# CurruntGetter.net
KiCad netlist of a schematic drawn in Altium Designer
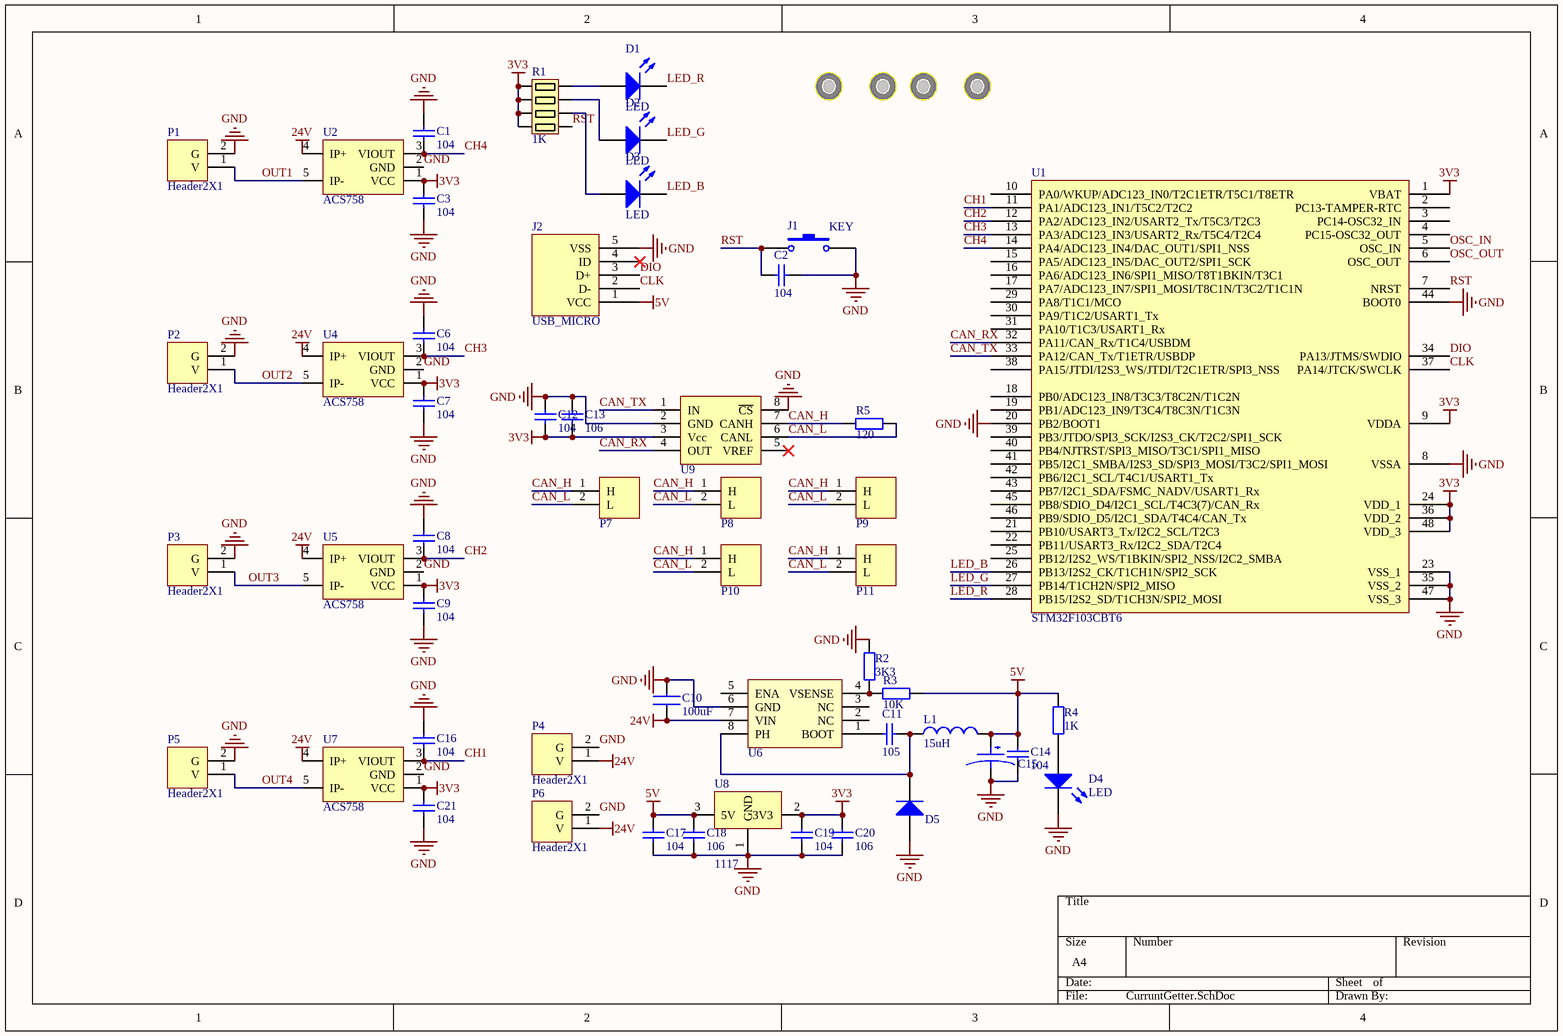
[diagram p0: CurruntGetter.SchDoc]

(export (version "E")
  (design (tool "Eeschema 10.0.6"))
  (components
    (comp (ref "1") (value "Via_M3") (footprint "Via_M3") (libsource (lib "SHAWN") (part "Via_M3")))
    (comp (ref "2") (value "Via_M3") (footprint "Via_M3") (libsource (lib "SHAWN") (part "Via_M3")))
    (comp (ref "3") (value "Via_M3") (footprint "Via_M3") (libsource (lib "SHAWN") (part "Via_M3")))
    (comp (ref "4") (value "Via_M3") (footprint "Via_M3") (libsource (lib "SHAWN") (part "Via_M3")))
    (comp (ref "C1")
      (value "104")
      (footprint "0603C")
      (description "0603/0805")
      (libsource (lib "SHAWN") (part "C_104"))
    )
    (comp (ref "C2")
      (value "104")
      (footprint "0603C")
      (description "0603/0805")
      (libsource (lib "SHAWN") (part "C_104"))
    )
    (comp (ref "C3")
      (value "104")
      (footprint "0603C")
      (description "0603/0805")
      (libsource (lib "SHAWN") (part "C_104"))
    )
    (comp (ref "C6")
      (value "104")
      (footprint "0603C")
      (description "0603/0805")
      (libsource (lib "SHAWN") (part "C_104"))
    )
    (comp (ref "C7")
      (value "104")
      (footprint "0603C")
      (description "0603/0805")
      (libsource (lib "SHAWN") (part "C_104"))
    )
    (comp (ref "C8")
      (value "104")
      (footprint "0603C")
      (description "0603/0805")
      (libsource (lib "SHAWN") (part "C_104"))
    )
    (comp (ref "C9")
      (value "104")
      (footprint "0603C")
      (description "0603/0805")
      (libsource (lib "SHAWN") (part "C_104"))
    )
    (comp (ref "C10") (value "100uF") (footprint "1201C") (libsource (lib "SHAWN") (part "CAP100uF")))
    (comp (ref "C11")
      (value "105")
      (footprint "0603C")
      (description "0603/0805")
      (libsource (lib "SHAWN") (part "C_104"))
    )
    (comp (ref "C12")
      (value "104")
      (footprint "0603C")
      (description "0603/0805")
      (libsource (lib "SHAWN") (part "C_104"))
    )
    (comp (ref "C13")
      (value "106")
      (footprint "0603C")
      (description "0603/0805")
      (libsource (lib "SHAWN") (part "C_106"))
    )
    (comp (ref "C14")
      (value "104")
      (footprint "0603C")
      (description "0603/0805")
      (libsource (lib "SHAWN") (part "C_104"))
    )
    (comp (ref "C15")
      (value "CAP_钽220")
      (footprint "cap_钽E封装")
      (description "CAP")
      (libsource (lib "SHAWN") (part "CAP_钽220"))
    )
    (comp (ref "C16")
      (value "104")
      (footprint "0603C")
      (description "0603/0805")
      (libsource (lib "SHAWN") (part "C_104"))
    )
    (comp (ref "C17")
      (value "104")
      (footprint "0603C")
      (description "0603/0805")
      (libsource (lib "SHAWN") (part "C_104"))
    )
    (comp (ref "C18")
      (value "106")
      (footprint "0603C")
      (description "0603/0805")
      (libsource (lib "SHAWN") (part "C_106"))
    )
    (comp (ref "C19")
      (value "104")
      (footprint "0603C")
      (description "0603/0805")
      (libsource (lib "SHAWN") (part "C_104"))
    )
    (comp (ref "C20")
      (value "106")
      (footprint "0603C")
      (description "0603/0805")
      (libsource (lib "SHAWN") (part "C_106"))
    )
    (comp (ref "C21")
      (value "104")
      (footprint "0603C")
      (description "0603/0805")
      (libsource (lib "SHAWN") (part "C_104"))
    )
    (comp (ref "D1") (value "LED") (footprint "LED_0603") (libsource (lib "SHAWN") (part "LED")))
    (comp (ref "D2") (value "LED") (footprint "LED_0603") (libsource (lib "SHAWN") (part "LED")))
    (comp (ref "D3") (value "LED") (footprint "LED_0603") (libsource (lib "SHAWN") (part "LED")))
    (comp (ref "D4") (value "LED") (footprint "LED_0603") (libsource (lib "SHAWN") (part "LED")))
    (comp (ref "D5")
      (value "Diode_SS34")
      (footprint "Diode_SS34")
      (description "肖特基二极管")
      (libsource (lib "SHAWN") (part "Diode_SS34"))
    )
    (comp (ref "J1") (value "KEY") (footprint "KEY") (libsource (lib "SHAWN") (part "KEY")))
    (comp (ref "J2") (value "USB_MICRO") (footprint "USB_MICRO") (libsource (lib "SHAWN") (part "USB_MICRO")))
    (comp (ref "L1")
      (value "15uH")
      (footprint "Inductor7.2X7.2")
      (description "屏蔽电感")
      (libsource (lib "SHAWN") (part "Inductor"))
    )
    (comp (ref "P1")
      (value "Header2X1")
      (footprint "Header_POWER")
      (description "power")
      (libsource (lib "SHAWN") (part "Header2X1"))
    )
    (comp (ref "P2")
      (value "Header2X1")
      (footprint "Header_POWER")
      (description "power")
      (libsource (lib "SHAWN") (part "Header2X1"))
    )
    (comp (ref "P3")
      (value "Header2X1")
      (footprint "Header_POWER")
      (description "power")
      (libsource (lib "SHAWN") (part "Header2X1"))
    )
    (comp (ref "P4")
      (value "Header2X1")
      (footprint "Header_POWER")
      (description "power")
      (libsource (lib "SHAWN") (part "Header2X1"))
    )
    (comp (ref "P5")
      (value "Header2X1")
      (footprint "Header_POWER")
      (description "power")
      (libsource (lib "SHAWN") (part "Header2X1"))
    )
    (comp (ref "P6")
      (value "Header2X1")
      (footprint "Header_POWER")
      (description "power")
      (libsource (lib "SHAWN") (part "Header2X1"))
    )
    (comp (ref "P7")
      (value "Header_CAN")
      (footprint "Header2_3002")
      (libsource (lib "SHAWN") (part "Header_CAN"))
    )
    (comp (ref "P8")
      (value "Header_CAN")
      (footprint "Header2_3002")
      (libsource (lib "SHAWN") (part "Header_CAN"))
    )
    (comp (ref "P9")
      (value "Header_CAN")
      (footprint "Header2_3002")
      (libsource (lib "SHAWN") (part "Header_CAN"))
    )
    (comp (ref "P10")
      (value "Header_CAN")
      (footprint "Header2_3002")
      (libsource (lib "SHAWN") (part "Header_CAN"))
    )
    (comp (ref "P11")
      (value "Header_CAN")
      (footprint "Header2_3002")
      (libsource (lib "SHAWN") (part "Header_CAN"))
    )
    (comp (ref "R1") (value "1K") (footprint "8P4R_0603") (libsource (lib "SHAWN") (part "R_8P4R")))
    (comp (ref "R2")
      (value "3K3")
      (footprint "0603R")
      (description "0603/0805")
      (libsource (lib "") (part "R_1"))
    )
    (comp (ref "R3")
      (value "10K")
      (footprint "0603R")
      (description "0603/0805")
      (libsource (lib "SHAWN") (part "R"))
    )
    (comp (ref "R4")
      (value "1K")
      (footprint "0603R")
      (description "0603/0805")
      (libsource (lib "") (part "R_1"))
    )
    (comp (ref "R5")
      (value "120")
      (footprint "0603R")
      (description "0603/0805")
      (libsource (lib "SHAWN") (part "R"))
    )
    (comp (ref "U1")
      (value "STM32F103CBT6")
      (footprint "LQFP_48")
      (description "48")
      (libsource (lib "SHAWN") (part "STM32F103CBT6"))
    )
    (comp (ref "U2") (value "ACS758") (footprint "PFF") (libsource (lib "SHAWN") (part "ACS758")))
    (comp (ref "U4") (value "ACS758") (footprint "PFF") (libsource (lib "SHAWN") (part "ACS758")))
    (comp (ref "U5") (value "ACS758") (footprint "PFF") (libsource (lib "SHAWN") (part "ACS758")))
    (comp (ref "U6")
      (value "TPS5430/5450")
      (footprint "TPS5430")
      (description "降压")
      (libsource (lib "SHAWN") (part "TPS5430/5450"))
    )
    (comp (ref "U7") (value "ACS758") (footprint "PFF") (libsource (lib "SHAWN") (part "ACS758")))
    (comp (ref "U8") (value "1117") (footprint "SOT-223") (libsource (lib "SHAWN") (part "AMS1117-3.3")))
    (comp (ref "U9")
      (value "VD230")
      (footprint "SO_8")
      (description "SO-8")
      (libsource (lib "SHAWN") (part "VD230"))
    )
  )
  (nets
    (net (code "1") (name "/CAN_H") (class "Default")
      (node (ref "P10") (pin "1") (pinfunction "H_1") (pintype "passive"))
      (node (ref "P11") (pin "1") (pinfunction "H_1") (pintype "passive"))
      (node (ref "P7") (pin "1") (pinfunction "H_1") (pintype "passive"))
      (node (ref "P8") (pin "1") (pinfunction "H_1") (pintype "passive"))
      (node (ref "P9") (pin "1") (pinfunction "H_1") (pintype "passive"))
      (node (ref "R5") (pin "2") (pinfunction "2_2") (pintype "passive"))
      (node (ref "U9") (pin "7") (pinfunction "CANH_7") (pintype "passive"))
    )
    (net (code "2") (name "/CAN_L") (class "Default")
      (node (ref "P10") (pin "2") (pinfunction "L_2") (pintype "passive"))
      (node (ref "P11") (pin "2") (pinfunction "L_2") (pintype "passive"))
      (node (ref "P7") (pin "2") (pinfunction "L_2") (pintype "passive"))
      (node (ref "P8") (pin "2") (pinfunction "L_2") (pintype "passive"))
      (node (ref "P9") (pin "2") (pinfunction "L_2") (pintype "passive"))
      (node (ref "R5") (pin "1") (pinfunction "1_1") (pintype "passive"))
      (node (ref "U9") (pin "6") (pinfunction "CANL_6") (pintype "passive"))
    )
    (net (code "3") (name "/CAN_RX") (class "Default")
      (node (ref "U1") (pin "32") (pinfunction "PA11/CAN_Rx/T1C4/USBDM_32") (pintype "passive"))
      (node (ref "U9") (pin "4") (pinfunction "OUT_4") (pintype "passive"))
    )
    (net (code "4") (name "/CAN_TX") (class "Default")
      (node (ref "U1") (pin "33") (pinfunction "PA12/CAN_Tx/T1ETR/USBDP_33") (pintype "passive"))
      (node (ref "U9") (pin "1") (pinfunction "IN_1") (pintype "passive"))
    )
    (net (code "5") (name "/CH1") (class "Default")
      (node (ref "C16") (pin "1") (pinfunction "1_1") (pintype "passive"))
      (node (ref "U1") (pin "11") (pinfunction "PA1/ADC123_IN1/T5C2/T2C2_11") (pintype "passive"))
      (node (ref "U7") (pin "3") (pinfunction "VIOUT_3") (pintype "passive"))
    )
    (net (code "6") (name "/CH2") (class "Default")
      (node (ref "C8") (pin "1") (pinfunction "1_1") (pintype "passive"))
      (node (ref "U1") (pin "12") (pinfunction "PA2/ADC123_IN2/USART2_Tx/T5C3/T2C3_12") (pintype "passive"))
      (node (ref "U5") (pin "3") (pinfunction "VIOUT_3") (pintype "passive"))
    )
    (net (code "7") (name "/CH3") (class "Default")
      (node (ref "C6") (pin "1") (pinfunction "1_1") (pintype "passive"))
      (node (ref "U1") (pin "13") (pinfunction "PA3/ADC123_IN3/USART2_Rx/T5C4/T2C4_13") (pintype "passive"))
      (node (ref "U4") (pin "3") (pinfunction "VIOUT_3") (pintype "passive"))
    )
    (net (code "8") (name "/CH4") (class "Default")
      (node (ref "C1") (pin "1") (pinfunction "1_1") (pintype "passive"))
      (node (ref "U1") (pin "14") (pinfunction "PA4/ADC123_IN4/DAC_OUT1/SPI1_NSS_14") (pintype "passive"))
      (node (ref "U2") (pin "3") (pinfunction "VIOUT_3") (pintype "passive"))
    )
    (net (code "9") (name "/CLK") (class "Default")
      (node (ref "J2") (pin "2") (pinfunction "D-_2") (pintype "passive"))
      (node (ref "U1") (pin "37") (pinfunction "PA14/JTCK/SWCLK_37") (pintype "passive"))
    )
    (net (code "10") (name "/DIO") (class "Default")
      (node (ref "J2") (pin "3") (pinfunction "D+_3") (pintype "passive"))
      (node (ref "U1") (pin "34") (pinfunction "PA13/JTMS/SWDIO_34") (pintype "passive"))
    )
    (net (code "11") (name "/LED_B") (class "Default")
      (node (ref "D3") (pin "2") (pinfunction "K_2") (pintype "passive"))
      (node (ref "U1") (pin "26") (pinfunction "PB13/I2S2_CK/T1CH1N/SPI2_SCK_26") (pintype "passive"))
    )
    (net (code "12") (name "/LED_G") (class "Default")
      (node (ref "D2") (pin "2") (pinfunction "K_2") (pintype "passive"))
      (node (ref "U1") (pin "27") (pinfunction "PB14/T1CH2N/SPI2_MISO_27") (pintype "passive"))
    )
    (net (code "13") (name "/LED_R") (class "Default")
      (node (ref "D1") (pin "2") (pinfunction "K_2") (pintype "passive"))
      (node (ref "U1") (pin "28") (pinfunction "PB15/I2S2_SD/T1CH3N/SPI2_MOSI_28") (pintype "passive"))
    )
    (net (code "14") (name "/OSC_IN") (class "Default")
      (node (ref "U1") (pin "5") (pinfunction "OSC_IN_5") (pintype "passive"))
    )
    (net (code "15") (name "/OSC_OUT") (class "Default")
      (node (ref "U1") (pin "6") (pinfunction "OSC_OUT_6") (pintype "passive"))
    )
    (net (code "16") (name "/OUT1") (class "Default")
      (node (ref "P1") (pin "1") (pinfunction "V_1") (pintype "passive"))
      (node (ref "U2") (pin "5") (pinfunction "IP-_5") (pintype "passive"))
    )
    (net (code "17") (name "/OUT2") (class "Default")
      (node (ref "P2") (pin "1") (pinfunction "V_1") (pintype "passive"))
      (node (ref "U4") (pin "5") (pinfunction "IP-_5") (pintype "passive"))
    )
    (net (code "18") (name "/OUT3") (class "Default")
      (node (ref "P3") (pin "1") (pinfunction "V_1") (pintype "passive"))
      (node (ref "U5") (pin "5") (pinfunction "IP-_5") (pintype "passive"))
    )
    (net (code "19") (name "/OUT4") (class "Default")
      (node (ref "P5") (pin "1") (pinfunction "V_1") (pintype "passive"))
      (node (ref "U7") (pin "5") (pinfunction "IP-_5") (pintype "passive"))
    )
    (net (code "20") (name "/RST") (class "Default")
      (node (ref "C2") (pin "1") (pinfunction "1_1") (pintype "passive"))
      (node (ref "J1") (pin "1") (pinfunction "1_1") (pintype "passive"))
      (node (ref "R1") (pin "5") (pinfunction "5_5") (pintype "passive"))
      (node (ref "U1") (pin "7") (pinfunction "NRST_7") (pintype "passive"))
    )
    (net (code "21") (name "3V3") (class "Default")
      (node (ref "C12") (pin "1") (pinfunction "1_1") (pintype "passive"))
      (node (ref "C13") (pin "1") (pinfunction "1_1") (pintype "passive"))
      (node (ref "C19") (pin "2") (pinfunction "2_2") (pintype "passive"))
      (node (ref "C20") (pin "2") (pinfunction "2_2") (pintype "passive"))
      (node (ref "C21") (pin "2") (pinfunction "2_2") (pintype "passive"))
      (node (ref "C3") (pin "2") (pinfunction "2_2") (pintype "passive"))
      (node (ref "C7") (pin "2") (pinfunction "2_2") (pintype "passive"))
      (node (ref "C9") (pin "2") (pinfunction "2_2") (pintype "passive"))
      (node (ref "R1") (pin "1") (pinfunction "1_1") (pintype "passive"))
      (node (ref "R1") (pin "2") (pinfunction "2_2") (pintype "passive"))
      (node (ref "R1") (pin "3") (pinfunction "3_3") (pintype "passive"))
      (node (ref "R1") (pin "4") (pinfunction "4_4") (pintype "passive"))
      (node (ref "U1") (pin "1") (pinfunction "VBAT_1") (pintype "passive"))
      (node (ref "U1") (pin "24") (pinfunction "VDD_1_24") (pintype "passive"))
      (node (ref "U1") (pin "36") (pinfunction "VDD_2_36") (pintype "passive"))
      (node (ref "U1") (pin "48") (pinfunction "VDD_3_48") (pintype "passive"))
      (node (ref "U1") (pin "9") (pinfunction "VDDA_9") (pintype "passive"))
      (node (ref "U2") (pin "1") (pinfunction "VCC_1") (pintype "passive"))
      (node (ref "U4") (pin "1") (pinfunction "VCC_1") (pintype "passive"))
      (node (ref "U5") (pin "1") (pinfunction "VCC_1") (pintype "passive"))
      (node (ref "U7") (pin "1") (pinfunction "VCC_1") (pintype "passive"))
      (node (ref "U8") (pin "2") (pinfunction "3V3_2") (pintype "passive"))
      (node (ref "U9") (pin "3") (pinfunction "Vcc_3") (pintype "passive"))
    )
    (net (code "22") (name "5V") (class "Default")
      (node (ref "C14") (pin "2") (pinfunction "2_2") (pintype "passive"))
      (node (ref "C15") (pin "2") (pinfunction "2_2") (pintype "passive"))
      (node (ref "C17") (pin "2") (pinfunction "2_2") (pintype "passive"))
      (node (ref "C18") (pin "2") (pinfunction "2_2") (pintype "passive"))
      (node (ref "J2") (pin "1") (pinfunction "VCC_1") (pintype "passive"))
      (node (ref "L1") (pin "2") (pinfunction "2_2") (pintype "passive"))
      (node (ref "R3") (pin "1") (pinfunction "1_1") (pintype "passive"))
      (node (ref "R4") (pin "2") (pinfunction "2_2") (pintype "passive"))
      (node (ref "U8") (pin "3") (pinfunction "5V_3") (pintype "passive"))
    )
    (net (code "23") (name "24V") (class "Default")
      (node (ref "C10") (pin "1") (pinfunction "1_1") (pintype "passive"))
      (node (ref "P4") (pin "1") (pinfunction "V_1") (pintype "passive"))
      (node (ref "P6") (pin "1") (pinfunction "V_1") (pintype "passive"))
      (node (ref "U2") (pin "4") (pinfunction "IP+_4") (pintype "passive"))
      (node (ref "U4") (pin "4") (pinfunction "IP+_4") (pintype "passive"))
      (node (ref "U5") (pin "4") (pinfunction "IP+_4") (pintype "passive"))
      (node (ref "U6") (pin "7") (pinfunction "VIN_7") (pintype "passive"))
      (node (ref "U7") (pin "4") (pinfunction "IP+_4") (pintype "passive"))
    )
    (net (code "24") (name "GND") (class "Default")
      (node (ref "C1") (pin "2") (pinfunction "2_2") (pintype "passive"))
      (node (ref "C10") (pin "2") (pinfunction "2_2") (pintype "passive"))
      (node (ref "C12") (pin "2") (pinfunction "2_2") (pintype "passive"))
      (node (ref "C13") (pin "2") (pinfunction "2_2") (pintype "passive"))
      (node (ref "C14") (pin "1") (pinfunction "1_1") (pintype "passive"))
      (node (ref "C15") (pin "1") (pinfunction "1_1") (pintype "passive"))
      (node (ref "C16") (pin "2") (pinfunction "2_2") (pintype "passive"))
      (node (ref "C17") (pin "1") (pinfunction "1_1") (pintype "passive"))
      (node (ref "C18") (pin "1") (pinfunction "1_1") (pintype "passive"))
      (node (ref "C19") (pin "1") (pinfunction "1_1") (pintype "passive"))
      (node (ref "C2") (pin "2") (pinfunction "2_2") (pintype "passive"))
      (node (ref "C20") (pin "1") (pinfunction "1_1") (pintype "passive"))
      (node (ref "C21") (pin "1") (pinfunction "1_1") (pintype "passive"))
      (node (ref "C3") (pin "1") (pinfunction "1_1") (pintype "passive"))
      (node (ref "C6") (pin "2") (pinfunction "2_2") (pintype "passive"))
      (node (ref "C7") (pin "1") (pinfunction "1_1") (pintype "passive"))
      (node (ref "C8") (pin "2") (pinfunction "2_2") (pintype "passive"))
      (node (ref "C9") (pin "1") (pinfunction "1_1") (pintype "passive"))
      (node (ref "D4") (pin "2") (pinfunction "K_2") (pintype "passive"))
      (node (ref "D5") (pin "1") (pinfunction "A_1") (pintype "passive"))
      (node (ref "J1") (pin "2") (pinfunction "2_2") (pintype "passive"))
      (node (ref "J2") (pin "5") (pinfunction "VSS_5") (pintype "passive"))
      (node (ref "P1") (pin "2") (pinfunction "G_2") (pintype "passive"))
      (node (ref "P2") (pin "2") (pinfunction "G_2") (pintype "passive"))
      (node (ref "P3") (pin "2") (pinfunction "G_2") (pintype "passive"))
      (node (ref "P4") (pin "2") (pinfunction "G_2") (pintype "passive"))
      (node (ref "P5") (pin "2") (pinfunction "G_2") (pintype "passive"))
      (node (ref "P6") (pin "2") (pinfunction "G_2") (pintype "passive"))
      (node (ref "R2") (pin "2") (pinfunction "2_2") (pintype "passive"))
      (node (ref "U1") (pin "20") (pinfunction "PB2/BOOT1_20") (pintype "passive"))
      (node (ref "U1") (pin "23") (pinfunction "VSS_1_23") (pintype "passive"))
      (node (ref "U1") (pin "35") (pinfunction "VSS_2_35") (pintype "passive"))
      (node (ref "U1") (pin "44") (pinfunction "BOOT0_44") (pintype "passive"))
      (node (ref "U1") (pin "47") (pinfunction "VSS_3_47") (pintype "passive"))
      (node (ref "U1") (pin "8") (pinfunction "VSSA_8") (pintype "passive"))
      (node (ref "U2") (pin "2") (pinfunction "GND_2") (pintype "passive"))
      (node (ref "U4") (pin "2") (pinfunction "GND_2") (pintype "passive"))
      (node (ref "U5") (pin "2") (pinfunction "GND_2") (pintype "passive"))
      (node (ref "U6") (pin "6") (pinfunction "GND_6") (pintype "passive"))
      (node (ref "U7") (pin "2") (pinfunction "GND_2") (pintype "passive"))
      (node (ref "U8") (pin "1") (pinfunction "GND_1") (pintype "passive"))
      (node (ref "U9") (pin "2") (pinfunction "GND_2") (pintype "passive"))
      (node (ref "U9") (pin "8") (pinfunction "~{CS}_8") (pintype "passive"))
    )
    (net (code "25") (name "Net-(D1-A)") (class "Default")
      (node (ref "D1") (pin "1") (pinfunction "A_1") (pintype "passive"))
      (node (ref "R1") (pin "8") (pinfunction "8_8") (pintype "passive"))
    )
    (net (code "26") (name "Net-(D2-A)") (class "Default")
      (node (ref "D2") (pin "1") (pinfunction "A_1") (pintype "passive"))
      (node (ref "R1") (pin "7") (pinfunction "7_7") (pintype "passive"))
    )
    (net (code "27") (name "Net-(D3-A)") (class "Default")
      (node (ref "D3") (pin "1") (pinfunction "A_1") (pintype "passive"))
      (node (ref "R1") (pin "6") (pinfunction "6_6") (pintype "passive"))
    )
    (net (code "28") (name "Net-(D4-A)") (class "Default")
      (node (ref "D4") (pin "1") (pinfunction "A_1") (pintype "passive"))
      (node (ref "R4") (pin "1") (pinfunction "1_1") (pintype "passive"))
    )
    (net (code "29") (name "Net-(D5-K)") (class "Default")
      (node (ref "C11") (pin "2") (pinfunction "2_2") (pintype "passive"))
      (node (ref "D5") (pin "2") (pinfunction "K_2") (pintype "passive"))
      (node (ref "L1") (pin "1") (pinfunction "1_1") (pintype "passive"))
      (node (ref "U6") (pin "8") (pinfunction "PH_8") (pintype "passive"))
    )
    (net (code "30") (name "Net-(U6-BOOT)") (class "Default")
      (node (ref "C11") (pin "1") (pinfunction "1_1") (pintype "passive"))
      (node (ref "U6") (pin "1") (pinfunction "BOOT_1") (pintype "passive"))
    )
    (net (code "31") (name "Net-(U6-VSENSE)") (class "Default")
      (node (ref "R2") (pin "1") (pinfunction "1_1") (pintype "passive"))
      (node (ref "R3") (pin "2") (pinfunction "2_2") (pintype "passive"))
      (node (ref "U6") (pin "4") (pinfunction "VSENSE_4") (pintype "passive"))
    )
    (net (code "32") (name "unconnected-(J2-ID-Pad4)") (class "Default")
      (node (ref "J2") (pin "4") (pinfunction "ID_4") (pintype "passive+no_connect"))
    )
    (net (code "33") (name "unconnected-(U1-PA0{slash}WKUP{slash}ADC123_IN0{slash}T2C1ETR{slash}T5C1{slash}T8ETR-Pad10)") (class "Default")
      (node (ref "U1") (pin "10") (pinfunction "PA0/WKUP/ADC123_IN0/T2C1ETR/T5C1/T8ETR_10") (pintype "passive"))
    )
    (net (code "34") (name "unconnected-(U1-PA5{slash}ADC123_IN5{slash}DAC_OUT2{slash}SPI1_SCK-Pad15)") (class "Default")
      (node (ref "U1") (pin "15") (pinfunction "PA5/ADC123_IN5/DAC_OUT2/SPI1_SCK_15") (pintype "passive"))
    )
    (net (code "35") (name "unconnected-(U1-PA6{slash}ADC123_IN6{slash}SPI1_MISO{slash}T8T1BKIN{slash}T3C1-Pad16)") (class "Default")
      (node (ref "U1") (pin "16") (pinfunction "PA6/ADC123_IN6/SPI1_MISO/T8T1BKIN/T3C1_16") (pintype "passive"))
    )
    (net (code "36") (name "unconnected-(U1-PA7{slash}ADC123_IN7{slash}SPI1_MOSI{slash}T8C1N{slash}T3C2{slash}T1C1N-Pad17)") (class "Default")
      (node (ref "U1") (pin "17") (pinfunction "PA7/ADC123_IN7/SPI1_MOSI/T8C1N/T3C2/T1C1N_17") (pintype "passive"))
    )
    (net (code "37") (name "unconnected-(U1-PA8{slash}T1C1{slash}MCO-Pad29)") (class "Default")
      (node (ref "U1") (pin "29") (pinfunction "PA8/T1C1/MCO_29") (pintype "passive"))
    )
    (net (code "38") (name "unconnected-(U1-PA9{slash}T1C2{slash}USART1_Tx-Pad30)") (class "Default")
      (node (ref "U1") (pin "30") (pinfunction "PA9/T1C2/USART1_Tx_30") (pintype "passive"))
    )
    (net (code "39") (name "unconnected-(U1-PA10{slash}T1C3{slash}USART1_Rx-Pad31)") (class "Default")
      (node (ref "U1") (pin "31") (pinfunction "PA10/T1C3/USART1_Rx_31") (pintype "passive"))
    )
    (net (code "40") (name "unconnected-(U1-PA15{slash}JTDI{slash}I2S3_WS{slash}JTDI{slash}T2C1ETR{slash}SPI3_NSS-Pad38)") (class "Default")
      (node (ref "U1") (pin "38") (pinfunction "PA15/JTDI/I2S3_WS/JTDI/T2C1ETR/SPI3_NSS_38") (pintype "passive"))
    )
    (net (code "41") (name "unconnected-(U1-PB0{slash}ADC123_IN8{slash}T3C3{slash}T8C2N{slash}T1C2N-Pad18)") (class "Default")
      (node (ref "U1") (pin "18") (pinfunction "PB0/ADC123_IN8/T3C3/T8C2N/T1C2N_18") (pintype "passive"))
    )
    (net (code "42") (name "unconnected-(U1-PB1{slash}ADC123_IN9{slash}T3C4{slash}T8C3N{slash}T1C3N-Pad19)") (class "Default")
      (node (ref "U1") (pin "19") (pinfunction "PB1/ADC123_IN9/T3C4/T8C3N/T1C3N_19") (pintype "passive"))
    )
    (net (code "43") (name "unconnected-(U1-PB3{slash}JTDO{slash}SPI3_SCK{slash}I2S3_CK{slash}T2C2{slash}SPI1_SCK-Pad39)") (class "Default")
      (node (ref "U1") (pin "39") (pinfunction "PB3/JTDO/SPI3_SCK/I2S3_CK/T2C2/SPI1_SCK_39") (pintype "passive"))
    )
    (net (code "44") (name "unconnected-(U1-PB4{slash}NJTRST{slash}SPI3_MISO{slash}T3C1{slash}SPI1_MISO-Pad40)") (class "Default")
      (node (ref "U1") (pin "40") (pinfunction "PB4/NJTRST/SPI3_MISO/T3C1/SPI1_MISO_40") (pintype "passive"))
    )
    (net (code "45") (name "unconnected-(U1-PB5{slash}I2C1_SMBA{slash}I2S3_SD{slash}SPI3_MOSI{slash}T3C2{slash}SPI1_MOSI-Pad41)") (class "Default")
      (node (ref "U1") (pin "41") (pinfunction "PB5/I2C1_SMBA/I2S3_SD/SPI3_MOSI/T3C2/SPI1_MOSI_41") (pintype "passive"))
    )
    (net (code "46") (name "unconnected-(U1-PB6{slash}I2C1_SCL{slash}T4C1{slash}USART1_Tx-Pad42)") (class "Default")
      (node (ref "U1") (pin "42") (pinfunction "PB6/I2C1_SCL/T4C1/USART1_Tx_42") (pintype "passive"))
    )
    (net (code "47") (name "unconnected-(U1-PB7{slash}I2C1_SDA{slash}FSMC_NADV{slash}USART1_Rx-Pad43)") (class "Default")
      (node (ref "U1") (pin "43") (pinfunction "PB7/I2C1_SDA/FSMC_NADV/USART1_Rx_43") (pintype "passive"))
    )
    (net (code "48") (name "unconnected-(U1-PB8{slash}SDIO_D4{slash}I2C1_SCL{slash}T4C3(7){slash}CAN_Rx-Pad45)") (class "Default")
      (node (ref "U1") (pin "45") (pinfunction "PB8/SDIO_D4/I2C1_SCL/T4C3(7)/CAN_Rx_45") (pintype "passive"))
    )
    (net (code "49") (name "unconnected-(U1-PB9{slash}SDIO_D5{slash}I2C1_SDA{slash}T4C4{slash}CAN_Tx-Pad46)") (class "Default")
      (node (ref "U1") (pin "46") (pinfunction "PB9/SDIO_D5/I2C1_SDA/T4C4/CAN_Tx_46") (pintype "passive"))
    )
    (net (code "50") (name "unconnected-(U1-PB10{slash}USART3_Tx{slash}I2C2_SCL{slash}T2C3-Pad21)") (class "Default")
      (node (ref "U1") (pin "21") (pinfunction "PB10/USART3_Tx/I2C2_SCL/T2C3_21") (pintype "passive"))
    )
    (net (code "51") (name "unconnected-(U1-PB11{slash}USART3_Rx{slash}I2C2_SDA{slash}T2C4-Pad22)") (class "Default")
      (node (ref "U1") (pin "22") (pinfunction "PB11/USART3_Rx/I2C2_SDA/T2C4_22") (pintype "passive"))
    )
    (net (code "52") (name "unconnected-(U1-PB12{slash}I2S2_WS{slash}T1BKIN{slash}SPI2_NSS{slash}I2C2_SMBA-Pad25)") (class "Default")
      (node (ref "U1") (pin "25") (pinfunction "PB12/I2S2_WS/T1BKIN/SPI2_NSS/I2C2_SMBA_25") (pintype "passive"))
    )
    (net (code "53") (name "unconnected-(U1-PC13-TAMPER-RTC-Pad2)") (class "Default")
      (node (ref "U1") (pin "2") (pinfunction "PC13-TAMPER-RTC_2") (pintype "passive"))
    )
    (net (code "54") (name "unconnected-(U1-PC14-OSC32_IN-Pad3)") (class "Default")
      (node (ref "U1") (pin "3") (pinfunction "PC14-OSC32_IN_3") (pintype "passive"))
    )
    (net (code "55") (name "unconnected-(U1-PC15-OSC32_OUT-Pad4)") (class "Default")
      (node (ref "U1") (pin "4") (pinfunction "PC15-OSC32_OUT_4") (pintype "passive"))
    )
    (net (code "56") (name "unconnected-(U6-ENA-Pad5)") (class "Default")
      (node (ref "U6") (pin "5") (pinfunction "ENA_5") (pintype "passive"))
    )
    (net (code "57") (name "unconnected-(U6-NC-Pad2)") (class "Default")
      (node (ref "U6") (pin "2") (pinfunction "NC_2") (pintype "passive"))
    )
    (net (code "58") (name "unconnected-(U6-NC-Pad3)") (class "Default")
      (node (ref "U6") (pin "3") (pinfunction "NC_3") (pintype "passive"))
    )
    (net (code "59") (name "unconnected-(U9-VREF-Pad5)") (class "Default")
      (node (ref "U9") (pin "5") (pinfunction "VREF_5") (pintype "passive+no_connect"))
    )
  )
)
